# 2022.net
KiCad netlist of a schematic drawn in EAGLE
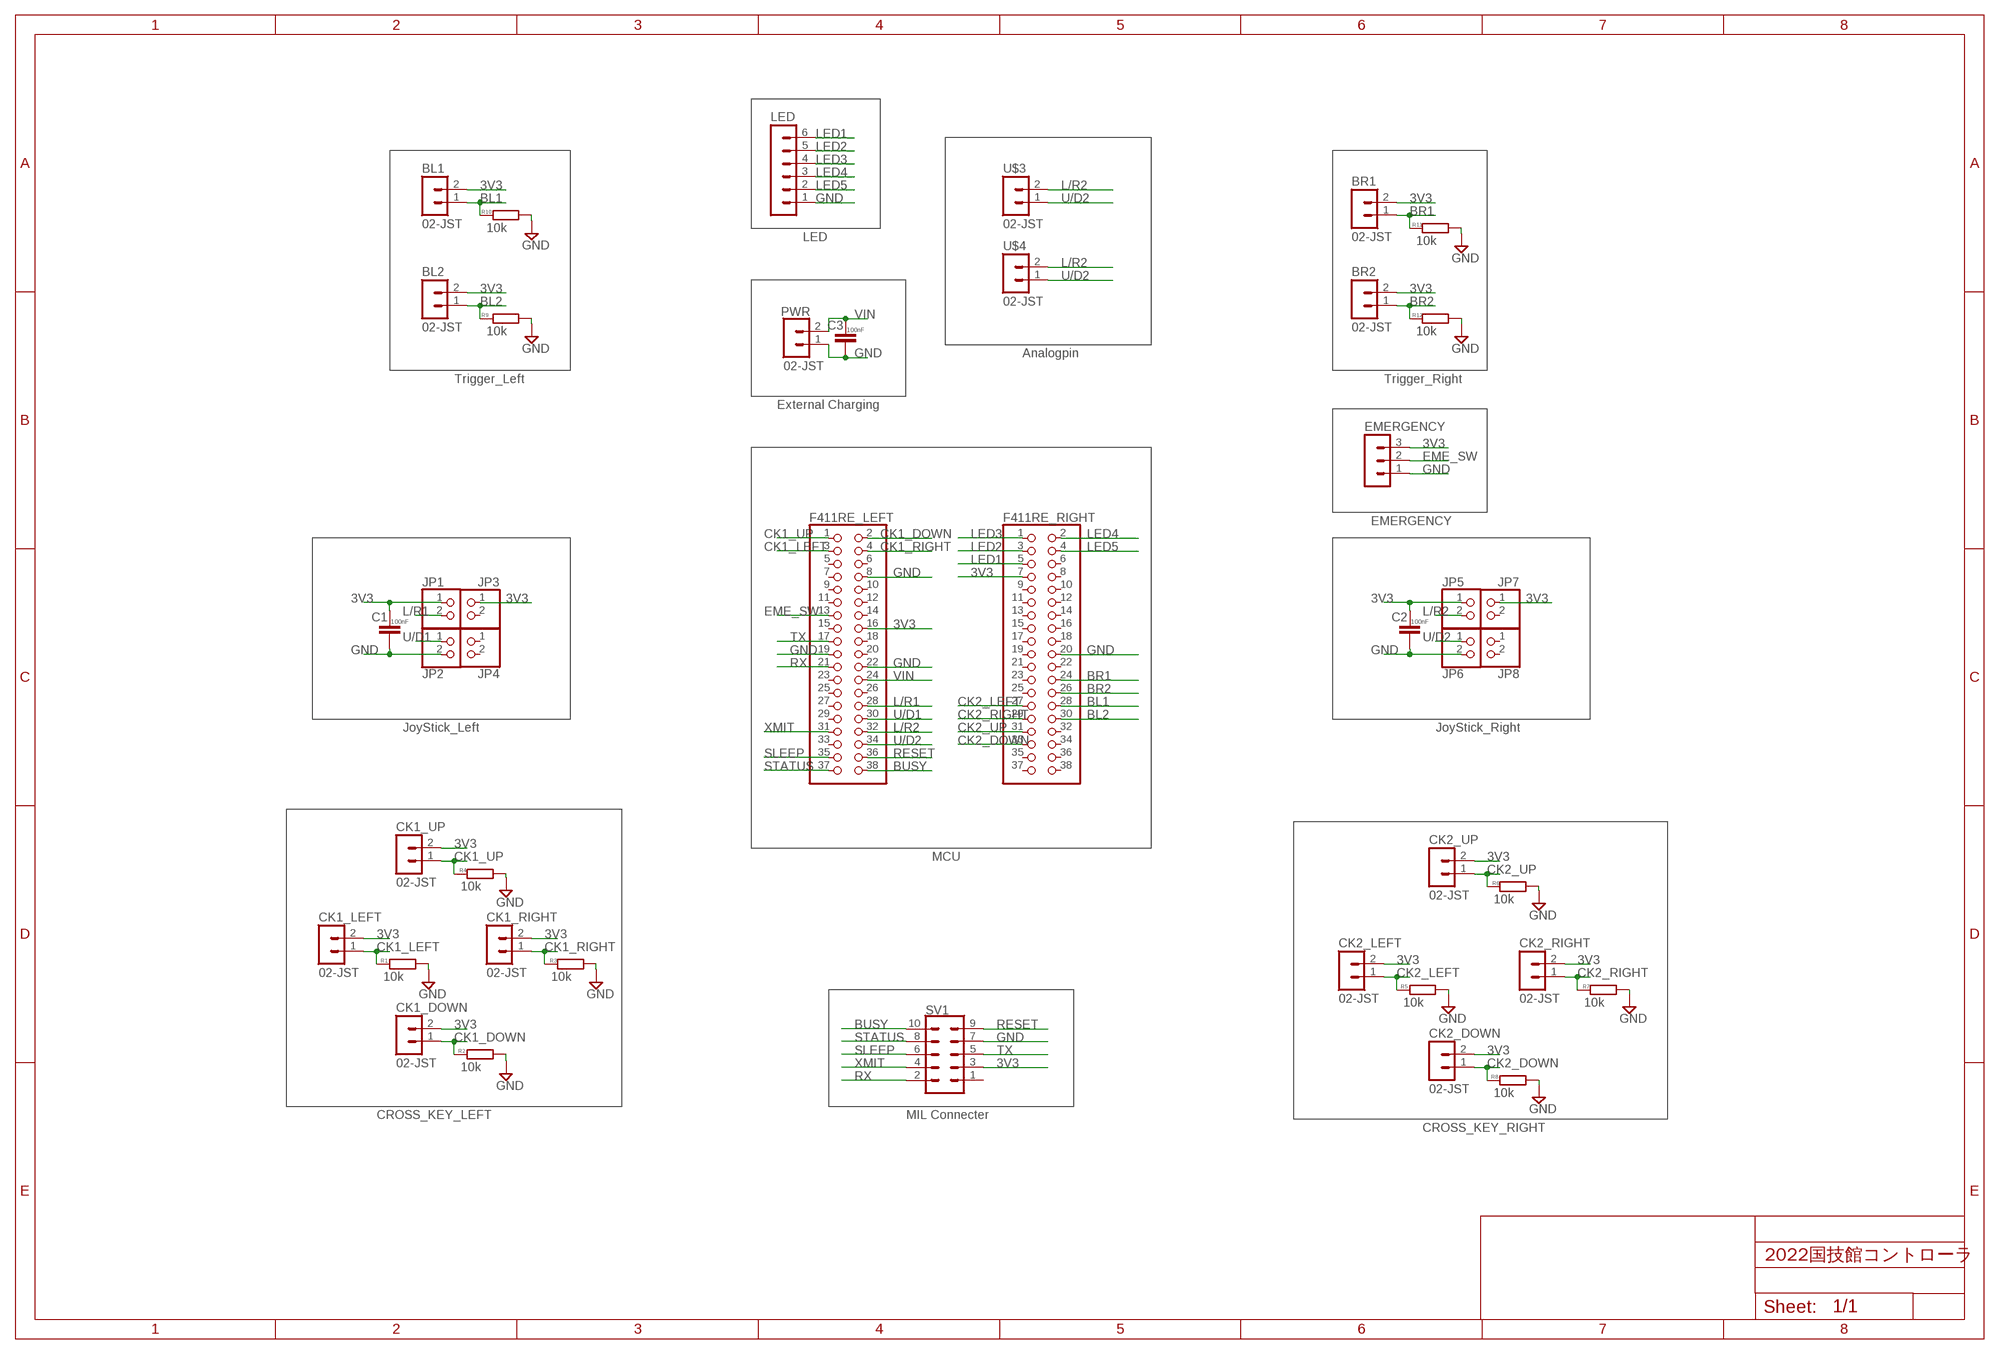
[diagram p0: schematic, sheet 1]

(export (version "E")
  (design (tool "Eeschema 10.0.6"))
  (components
    (comp (ref "BL1")
      (value "02-JST")
      (footprint "eagle-import:B2B-XH")
      (libsource (lib "eagle-import") (part "02-JST"))
    )
    (comp (ref "BL2")
      (value "02-JST")
      (footprint "eagle-import:B2B-XH")
      (libsource (lib "eagle-import") (part "02-JST"))
    )
    (comp (ref "BR1")
      (value "02-JST")
      (footprint "eagle-import:B2B-XH")
      (libsource (lib "eagle-import") (part "02-JST"))
    )
    (comp (ref "BR2")
      (value "02-JST")
      (footprint "eagle-import:B2B-XH")
      (libsource (lib "eagle-import") (part "02-JST"))
    )
    (comp (ref "C1")
      (value "100nF")
      (footprint "eagle-import:C025-024X044")
      (libsource (lib "eagle-import") (part "C-EU025-024X044"))
    )
    (comp (ref "C2")
      (value "100nF")
      (footprint "eagle-import:C025-024X044")
      (libsource (lib "eagle-import") (part "C-EU025-024X044"))
    )
    (comp (ref "C3")
      (value "100nF")
      (footprint "eagle-import:C025-024X044")
      (libsource (lib "eagle-import") (part "C-EU025-024X044"))
    )
    (comp (ref "CK1_DOWN")
      (value "02-JST")
      (footprint "eagle-import:B2B-XH")
      (libsource (lib "eagle-import") (part "02-JST"))
    )
    (comp (ref "CK1_LEFT")
      (value "02-JST")
      (footprint "eagle-import:B2B-XH")
      (libsource (lib "eagle-import") (part "02-JST"))
    )
    (comp (ref "CK1_RIGHT")
      (value "02-JST")
      (footprint "eagle-import:B2B-XH")
      (libsource (lib "eagle-import") (part "02-JST"))
    )
    (comp (ref "CK1_UP")
      (value "02-JST")
      (footprint "eagle-import:B2B-XH")
      (libsource (lib "eagle-import") (part "02-JST"))
    )
    (comp (ref "CK2_DOWN")
      (value "02-JST")
      (footprint "eagle-import:B2B-XH")
      (libsource (lib "eagle-import") (part "02-JST"))
    )
    (comp (ref "CK2_LEFT")
      (value "02-JST")
      (footprint "eagle-import:B2B-XH")
      (libsource (lib "eagle-import") (part "02-JST"))
    )
    (comp (ref "CK2_RIGHT")
      (value "02-JST")
      (footprint "eagle-import:B2B-XH")
      (libsource (lib "eagle-import") (part "02-JST"))
    )
    (comp (ref "CK2_UP")
      (value "02-JST")
      (footprint "eagle-import:B2B-XH")
      (libsource (lib "eagle-import") (part "02-JST"))
    )
    (comp (ref "EMERGENCY")
      (value "03-JST")
      (footprint "eagle-import:B3B-XH")
      (libsource (lib "eagle-import") (part "03-JST"))
    )
    (comp (ref "F411RE_LEFT")
      (value "PINHD-2X19")
      (footprint "eagle-import:2X19")
      (libsource (lib "eagle-import") (part "PINHD-2X19"))
    )
    (comp (ref "F411RE_RIGHT")
      (value "PINHD-2X19")
      (footprint "eagle-import:2X19")
      (libsource (lib "eagle-import") (part "PINHD-2X19"))
    )
    (comp (ref "JP1")
      (value "PINHD-1X2")
      (footprint "eagle-import:1X02")
      (libsource (lib "eagle-import") (part "PINHD-1X2"))
    )
    (comp (ref "JP2")
      (value "PINHD-1X2")
      (footprint "eagle-import:1X02")
      (libsource (lib "eagle-import") (part "PINHD-1X2"))
    )
    (comp (ref "JP3")
      (value "PINHD-1X2")
      (footprint "eagle-import:1X02")
      (libsource (lib "eagle-import") (part "PINHD-1X2"))
    )
    (comp (ref "JP4")
      (value "PINHD-1X2")
      (footprint "eagle-import:1X02")
      (libsource (lib "eagle-import") (part "PINHD-1X2"))
    )
    (comp (ref "JP5")
      (value "PINHD-1X2")
      (footprint "eagle-import:1X02")
      (libsource (lib "eagle-import") (part "PINHD-1X2"))
    )
    (comp (ref "JP6")
      (value "PINHD-1X2")
      (footprint "eagle-import:1X02")
      (libsource (lib "eagle-import") (part "PINHD-1X2"))
    )
    (comp (ref "JP7")
      (value "PINHD-1X2")
      (footprint "eagle-import:1X02")
      (libsource (lib "eagle-import") (part "PINHD-1X2"))
    )
    (comp (ref "JP8")
      (value "PINHD-1X2")
      (footprint "eagle-import:1X02")
      (libsource (lib "eagle-import") (part "PINHD-1X2"))
    )
    (comp (ref "LED")
      (value "06-JST")
      (footprint "eagle-import:B6B-XH")
      (libsource (lib "eagle-import") (part "06-JST"))
    )
    (comp (ref "PWR")
      (value "02-JST")
      (footprint "eagle-import:B2B-XH")
      (libsource (lib "eagle-import") (part "con-jst-xh (1)_02-JST"))
    )
    (comp (ref "R1")
      (value "10k")
      (footprint "eagle-import:0204_7")
      (libsource (lib "eagle-import") (part "R-EU_0204/7"))
    )
    (comp (ref "R2")
      (value "10k")
      (footprint "eagle-import:0204_7")
      (libsource (lib "eagle-import") (part "R-EU_0204/7"))
    )
    (comp (ref "R3")
      (value "10k")
      (footprint "eagle-import:0204_7")
      (libsource (lib "eagle-import") (part "R-EU_0204/7"))
    )
    (comp (ref "R4")
      (value "10k")
      (footprint "eagle-import:0204_7")
      (libsource (lib "eagle-import") (part "R-EU_0204/7"))
    )
    (comp (ref "R5")
      (value "10k")
      (footprint "eagle-import:0204_7")
      (libsource (lib "eagle-import") (part "R-EU_0204/7"))
    )
    (comp (ref "R6")
      (value "10k")
      (footprint "eagle-import:0204_7")
      (libsource (lib "eagle-import") (part "R-EU_0204/7"))
    )
    (comp (ref "R7")
      (value "10k")
      (footprint "eagle-import:0204_7")
      (libsource (lib "eagle-import") (part "R-EU_0204/7"))
    )
    (comp (ref "R8")
      (value "10k")
      (footprint "eagle-import:0204_7")
      (libsource (lib "eagle-import") (part "R-EU_0204/7"))
    )
    (comp (ref "R9")
      (value "10k")
      (footprint "eagle-import:0204_7")
      (libsource (lib "eagle-import") (part "R-EU_0204/7"))
    )
    (comp (ref "R10")
      (value "10k")
      (footprint "eagle-import:0204_7")
      (libsource (lib "eagle-import") (part "R-EU_0204/7"))
    )
    (comp (ref "R11")
      (value "10k")
      (footprint "eagle-import:0204_7")
      (libsource (lib "eagle-import") (part "R-EU_0204/7"))
    )
    (comp (ref "R12")
      (value "10k")
      (footprint "eagle-import:0204_7")
      (libsource (lib "eagle-import") (part "R-EU_0204/7"))
    )
    (comp (ref "SV1")
      (value "ML10")
      (footprint "eagle-import:ML10")
      (libsource (lib "eagle-import") (part "ML10"))
    )
    (comp (ref "U$3")
      (value "02-JST")
      (footprint "eagle-import:B2B-XH")
      (libsource (lib "eagle-import") (part "con-jst-xh (1)_02-JST"))
    )
    (comp (ref "U$4")
      (value "02-JST")
      (footprint "eagle-import:B2B-XH")
      (libsource (lib "eagle-import") (part "con-jst-xh (1)_02-JST"))
    )
  )
  (nets
    (net (code "1") (name "/3V3") (class "Default")
      (node (ref "BL1") (pin "2") (pinfunction "2_2") (pintype "passive"))
      (node (ref "BL2") (pin "2") (pinfunction "2_2") (pintype "passive"))
      (node (ref "BR1") (pin "2") (pinfunction "2_2") (pintype "passive"))
      (node (ref "BR2") (pin "2") (pinfunction "2_2") (pintype "passive"))
      (node (ref "C1") (pin "1") (pinfunction "1_1") (pintype "passive"))
      (node (ref "C2") (pin "1") (pinfunction "1_1") (pintype "passive"))
      (node (ref "CK1_DOWN") (pin "2") (pinfunction "2_2") (pintype "passive"))
      (node (ref "CK1_LEFT") (pin "2") (pinfunction "2_2") (pintype "passive"))
      (node (ref "CK1_RIGHT") (pin "2") (pinfunction "2_2") (pintype "passive"))
      (node (ref "CK1_UP") (pin "2") (pinfunction "2_2") (pintype "passive"))
      (node (ref "CK2_DOWN") (pin "2") (pinfunction "2_2") (pintype "passive"))
      (node (ref "CK2_LEFT") (pin "2") (pinfunction "2_2") (pintype "passive"))
      (node (ref "CK2_RIGHT") (pin "2") (pinfunction "2_2") (pintype "passive"))
      (node (ref "CK2_UP") (pin "2") (pinfunction "2_2") (pintype "passive"))
      (node (ref "EMERGENCY") (pin "3") (pinfunction "3_3") (pintype "passive"))
      (node (ref "F411RE_LEFT") (pin "16") (pinfunction "16_16") (pintype "passive"))
      (node (ref "F411RE_RIGHT") (pin "7") (pinfunction "7_7") (pintype "passive"))
      (node (ref "JP1") (pin "1") (pinfunction "1_1") (pintype "passive"))
      (node (ref "JP3") (pin "1") (pinfunction "1_1") (pintype "passive"))
      (node (ref "JP5") (pin "1") (pinfunction "1_1") (pintype "passive"))
      (node (ref "JP7") (pin "1") (pinfunction "1_1") (pintype "passive"))
      (node (ref "SV1") (pin "3") (pinfunction "3_3") (pintype "passive"))
    )
    (net (code "2") (name "/BL1") (class "Default")
      (node (ref "BL1") (pin "1") (pinfunction "1_1") (pintype "passive"))
      (node (ref "F411RE_RIGHT") (pin "28") (pinfunction "28_28") (pintype "passive"))
      (node (ref "R10") (pin "1") (pinfunction "1_1") (pintype "passive"))
    )
    (net (code "3") (name "/BL2") (class "Default")
      (node (ref "BL2") (pin "1") (pinfunction "1_1") (pintype "passive"))
      (node (ref "F411RE_RIGHT") (pin "30") (pinfunction "30_30") (pintype "passive"))
      (node (ref "R9") (pin "1") (pinfunction "1_1") (pintype "passive"))
    )
    (net (code "4") (name "/BR1") (class "Default")
      (node (ref "BR1") (pin "1") (pinfunction "1_1") (pintype "passive"))
      (node (ref "F411RE_RIGHT") (pin "24") (pinfunction "24_24") (pintype "passive"))
      (node (ref "R11") (pin "1") (pinfunction "1_1") (pintype "passive"))
    )
    (net (code "5") (name "/BR2") (class "Default")
      (node (ref "BR2") (pin "1") (pinfunction "1_1") (pintype "passive"))
      (node (ref "F411RE_RIGHT") (pin "26") (pinfunction "26_26") (pintype "passive"))
      (node (ref "R12") (pin "1") (pinfunction "1_1") (pintype "passive"))
    )
    (net (code "6") (name "/BUSY") (class "Default")
      (node (ref "F411RE_LEFT") (pin "38") (pinfunction "38_38") (pintype "passive"))
      (node (ref "SV1") (pin "10") (pinfunction "10_10") (pintype "passive"))
    )
    (net (code "7") (name "/CK1_DOWN") (class "Default")
      (node (ref "CK1_DOWN") (pin "1") (pinfunction "1_1") (pintype "passive"))
      (node (ref "F411RE_LEFT") (pin "2") (pinfunction "2_2") (pintype "passive"))
      (node (ref "R2") (pin "1") (pinfunction "1_1") (pintype "passive"))
    )
    (net (code "8") (name "/CK1_LEFT") (class "Default")
      (node (ref "CK1_LEFT") (pin "1") (pinfunction "1_1") (pintype "passive"))
      (node (ref "F411RE_LEFT") (pin "3") (pinfunction "3_3") (pintype "passive"))
      (node (ref "R1") (pin "1") (pinfunction "1_1") (pintype "passive"))
    )
    (net (code "9") (name "/CK1_RIGHT") (class "Default")
      (node (ref "CK1_RIGHT") (pin "1") (pinfunction "1_1") (pintype "passive"))
      (node (ref "F411RE_LEFT") (pin "4") (pinfunction "4_4") (pintype "passive"))
      (node (ref "R3") (pin "1") (pinfunction "1_1") (pintype "passive"))
    )
    (net (code "10") (name "/CK1_UP") (class "Default")
      (node (ref "CK1_UP") (pin "1") (pinfunction "1_1") (pintype "passive"))
      (node (ref "F411RE_LEFT") (pin "1") (pinfunction "1_1") (pintype "passive"))
      (node (ref "R4") (pin "1") (pinfunction "1_1") (pintype "passive"))
    )
    (net (code "11") (name "/CK2_DOWN") (class "Default")
      (node (ref "CK2_DOWN") (pin "1") (pinfunction "1_1") (pintype "passive"))
      (node (ref "F411RE_RIGHT") (pin "33") (pinfunction "33_33") (pintype "passive"))
      (node (ref "R8") (pin "1") (pinfunction "1_1") (pintype "passive"))
    )
    (net (code "12") (name "/CK2_LEFT") (class "Default")
      (node (ref "CK2_LEFT") (pin "1") (pinfunction "1_1") (pintype "passive"))
      (node (ref "F411RE_RIGHT") (pin "27") (pinfunction "27_27") (pintype "passive"))
      (node (ref "R5") (pin "1") (pinfunction "1_1") (pintype "passive"))
    )
    (net (code "13") (name "/CK2_RIGHT") (class "Default")
      (node (ref "CK2_RIGHT") (pin "1") (pinfunction "1_1") (pintype "passive"))
      (node (ref "F411RE_RIGHT") (pin "29") (pinfunction "29_29") (pintype "passive"))
      (node (ref "R7") (pin "1") (pinfunction "1_1") (pintype "passive"))
    )
    (net (code "14") (name "/CK2_UP") (class "Default")
      (node (ref "CK2_UP") (pin "1") (pinfunction "1_1") (pintype "passive"))
      (node (ref "F411RE_RIGHT") (pin "31") (pinfunction "31_31") (pintype "passive"))
      (node (ref "R6") (pin "1") (pinfunction "1_1") (pintype "passive"))
    )
    (net (code "15") (name "/EME_SW") (class "Default")
      (node (ref "EMERGENCY") (pin "2") (pinfunction "2_2") (pintype "passive"))
      (node (ref "F411RE_LEFT") (pin "13") (pinfunction "13_13") (pintype "passive"))
    )
    (net (code "16") (name "/LED1") (class "Default")
      (node (ref "F411RE_RIGHT") (pin "5") (pinfunction "5_5") (pintype "passive"))
      (node (ref "LED") (pin "6") (pinfunction "6_6") (pintype "passive"))
    )
    (net (code "17") (name "/LED2") (class "Default")
      (node (ref "F411RE_RIGHT") (pin "3") (pinfunction "3_3") (pintype "passive"))
      (node (ref "LED") (pin "5") (pinfunction "5_5") (pintype "passive"))
    )
    (net (code "18") (name "/LED3") (class "Default")
      (node (ref "F411RE_RIGHT") (pin "1") (pinfunction "1_1") (pintype "passive"))
      (node (ref "LED") (pin "4") (pinfunction "4_4") (pintype "passive"))
    )
    (net (code "19") (name "/LED4") (class "Default")
      (node (ref "F411RE_RIGHT") (pin "2") (pinfunction "2_2") (pintype "passive"))
      (node (ref "LED") (pin "3") (pinfunction "3_3") (pintype "passive"))
    )
    (net (code "20") (name "/LED5") (class "Default")
      (node (ref "F411RE_RIGHT") (pin "4") (pinfunction "4_4") (pintype "passive"))
      (node (ref "LED") (pin "2") (pinfunction "2_2") (pintype "passive"))
    )
    (net (code "21") (name "/L{slash}R1") (class "Default")
      (node (ref "F411RE_LEFT") (pin "28") (pinfunction "28_28") (pintype "passive"))
      (node (ref "JP1") (pin "2") (pinfunction "2_2") (pintype "passive"))
    )
    (net (code "22") (name "/L{slash}R2") (class "Default")
      (node (ref "F411RE_LEFT") (pin "32") (pinfunction "32_32") (pintype "passive"))
      (node (ref "JP5") (pin "2") (pinfunction "2_2") (pintype "passive"))
      (node (ref "U$3") (pin "2") (pinfunction "2_2") (pintype "passive"))
      (node (ref "U$4") (pin "2") (pinfunction "2_2") (pintype "passive"))
    )
    (net (code "23") (name "/RESET") (class "Default")
      (node (ref "F411RE_LEFT") (pin "36") (pinfunction "36_36") (pintype "passive"))
      (node (ref "SV1") (pin "9") (pinfunction "9_9") (pintype "passive"))
    )
    (net (code "24") (name "/RX") (class "Default")
      (node (ref "F411RE_LEFT") (pin "21") (pinfunction "21_21") (pintype "passive"))
      (node (ref "SV1") (pin "2") (pinfunction "2_2") (pintype "passive"))
    )
    (net (code "25") (name "/SLEEP") (class "Default")
      (node (ref "F411RE_LEFT") (pin "35") (pinfunction "35_35") (pintype "passive"))
      (node (ref "SV1") (pin "6") (pinfunction "6_6") (pintype "passive"))
    )
    (net (code "26") (name "/STATUS") (class "Default")
      (node (ref "F411RE_LEFT") (pin "37") (pinfunction "37_37") (pintype "passive"))
      (node (ref "SV1") (pin "8") (pinfunction "8_8") (pintype "passive"))
    )
    (net (code "27") (name "/TX") (class "Default")
      (node (ref "F411RE_LEFT") (pin "17") (pinfunction "17_17") (pintype "passive"))
      (node (ref "SV1") (pin "5") (pinfunction "5_5") (pintype "passive"))
    )
    (net (code "28") (name "/U{slash}D1") (class "Default")
      (node (ref "F411RE_LEFT") (pin "30") (pinfunction "30_30") (pintype "passive"))
      (node (ref "JP2") (pin "1") (pinfunction "1_1") (pintype "passive"))
    )
    (net (code "29") (name "/U{slash}D2") (class "Default")
      (node (ref "F411RE_LEFT") (pin "34") (pinfunction "34_34") (pintype "passive"))
      (node (ref "JP6") (pin "1") (pinfunction "1_1") (pintype "passive"))
      (node (ref "U$3") (pin "1") (pinfunction "1_1") (pintype "passive"))
      (node (ref "U$4") (pin "1") (pinfunction "1_1") (pintype "passive"))
    )
    (net (code "30") (name "/VIN") (class "Default")
      (node (ref "C3") (pin "1") (pinfunction "1_1") (pintype "passive"))
      (node (ref "F411RE_LEFT") (pin "24") (pinfunction "24_24") (pintype "passive"))
      (node (ref "PWR") (pin "2") (pinfunction "2_2") (pintype "passive"))
    )
    (net (code "31") (name "/XMIT") (class "Default")
      (node (ref "F411RE_LEFT") (pin "31") (pinfunction "31_31") (pintype "passive"))
      (node (ref "SV1") (pin "4") (pinfunction "4_4") (pintype "passive"))
    )
    (net (code "32") (name "GND") (class "Default")
      (node (ref "C1") (pin "2") (pinfunction "2_2") (pintype "passive"))
      (node (ref "C2") (pin "2") (pinfunction "2_2") (pintype "passive"))
      (node (ref "C3") (pin "2") (pinfunction "2_2") (pintype "passive"))
      (node (ref "EMERGENCY") (pin "1") (pinfunction "1_1") (pintype "passive"))
      (node (ref "F411RE_LEFT") (pin "19") (pinfunction "19_19") (pintype "passive"))
      (node (ref "F411RE_LEFT") (pin "22") (pinfunction "22_22") (pintype "passive"))
      (node (ref "F411RE_LEFT") (pin "8") (pinfunction "8_8") (pintype "passive"))
      (node (ref "F411RE_RIGHT") (pin "20") (pinfunction "20_20") (pintype "passive"))
      (node (ref "JP2") (pin "2") (pinfunction "2_2") (pintype "passive"))
      (node (ref "JP6") (pin "2") (pinfunction "2_2") (pintype "passive"))
      (node (ref "LED") (pin "1") (pinfunction "1_1") (pintype "passive"))
      (node (ref "PWR") (pin "1") (pinfunction "1_1") (pintype "passive"))
      (node (ref "R1") (pin "2") (pinfunction "2_2") (pintype "passive"))
      (node (ref "R10") (pin "2") (pinfunction "2_2") (pintype "passive"))
      (node (ref "R11") (pin "2") (pinfunction "2_2") (pintype "passive"))
      (node (ref "R12") (pin "2") (pinfunction "2_2") (pintype "passive"))
      (node (ref "R2") (pin "2") (pinfunction "2_2") (pintype "passive"))
      (node (ref "R3") (pin "2") (pinfunction "2_2") (pintype "passive"))
      (node (ref "R4") (pin "2") (pinfunction "2_2") (pintype "passive"))
      (node (ref "R5") (pin "2") (pinfunction "2_2") (pintype "passive"))
      (node (ref "R6") (pin "2") (pinfunction "2_2") (pintype "passive"))
      (node (ref "R7") (pin "2") (pinfunction "2_2") (pintype "passive"))
      (node (ref "R8") (pin "2") (pinfunction "2_2") (pintype "passive"))
      (node (ref "R9") (pin "2") (pinfunction "2_2") (pintype "passive"))
      (node (ref "SV1") (pin "7") (pinfunction "7_7") (pintype "passive"))
    )
    (net (code "33") (name "unconnected-(F411RE_LEFT-Pad5)") (class "Default")
      (node (ref "F411RE_LEFT") (pin "5") (pinfunction "5_5") (pintype "passive"))
    )
    (net (code "34") (name "unconnected-(F411RE_LEFT-Pad6)") (class "Default")
      (node (ref "F411RE_LEFT") (pin "6") (pinfunction "6_6") (pintype "passive"))
    )
    (net (code "35") (name "unconnected-(F411RE_LEFT-Pad7)") (class "Default")
      (node (ref "F411RE_LEFT") (pin "7") (pinfunction "7_7") (pintype "passive"))
    )
    (net (code "36") (name "unconnected-(F411RE_LEFT-Pad9)") (class "Default")
      (node (ref "F411RE_LEFT") (pin "9") (pinfunction "9_9") (pintype "passive"))
    )
    (net (code "37") (name "unconnected-(F411RE_LEFT-Pad10)") (class "Default")
      (node (ref "F411RE_LEFT") (pin "10") (pinfunction "10_10") (pintype "passive"))
    )
    (net (code "38") (name "unconnected-(F411RE_LEFT-Pad11)") (class "Default")
      (node (ref "F411RE_LEFT") (pin "11") (pinfunction "11_11") (pintype "passive"))
    )
    (net (code "39") (name "unconnected-(F411RE_LEFT-Pad12)") (class "Default")
      (node (ref "F411RE_LEFT") (pin "12") (pinfunction "12_12") (pintype "passive"))
    )
    (net (code "40") (name "unconnected-(F411RE_LEFT-Pad14)") (class "Default")
      (node (ref "F411RE_LEFT") (pin "14") (pinfunction "14_14") (pintype "passive"))
    )
    (net (code "41") (name "unconnected-(F411RE_LEFT-Pad15)") (class "Default")
      (node (ref "F411RE_LEFT") (pin "15") (pinfunction "15_15") (pintype "passive"))
    )
    (net (code "42") (name "unconnected-(F411RE_LEFT-Pad18)") (class "Default")
      (node (ref "F411RE_LEFT") (pin "18") (pinfunction "18_18") (pintype "passive"))
    )
    (net (code "43") (name "unconnected-(F411RE_LEFT-Pad20)") (class "Default")
      (node (ref "F411RE_LEFT") (pin "20") (pinfunction "20_20") (pintype "passive"))
    )
    (net (code "44") (name "unconnected-(F411RE_LEFT-Pad23)") (class "Default")
      (node (ref "F411RE_LEFT") (pin "23") (pinfunction "23_23") (pintype "passive"))
    )
    (net (code "45") (name "unconnected-(F411RE_LEFT-Pad25)") (class "Default")
      (node (ref "F411RE_LEFT") (pin "25") (pinfunction "25_25") (pintype "passive"))
    )
    (net (code "46") (name "unconnected-(F411RE_LEFT-Pad26)") (class "Default")
      (node (ref "F411RE_LEFT") (pin "26") (pinfunction "26_26") (pintype "passive"))
    )
    (net (code "47") (name "unconnected-(F411RE_LEFT-Pad27)") (class "Default")
      (node (ref "F411RE_LEFT") (pin "27") (pinfunction "27_27") (pintype "passive"))
    )
    (net (code "48") (name "unconnected-(F411RE_LEFT-Pad29)") (class "Default")
      (node (ref "F411RE_LEFT") (pin "29") (pinfunction "29_29") (pintype "passive"))
    )
    (net (code "49") (name "unconnected-(F411RE_LEFT-Pad33)") (class "Default")
      (node (ref "F411RE_LEFT") (pin "33") (pinfunction "33_33") (pintype "passive"))
    )
    (net (code "50") (name "unconnected-(F411RE_RIGHT-Pad6)") (class "Default")
      (node (ref "F411RE_RIGHT") (pin "6") (pinfunction "6_6") (pintype "passive"))
    )
    (net (code "51") (name "unconnected-(F411RE_RIGHT-Pad8)") (class "Default")
      (node (ref "F411RE_RIGHT") (pin "8") (pinfunction "8_8") (pintype "passive"))
    )
    (net (code "52") (name "unconnected-(F411RE_RIGHT-Pad9)") (class "Default")
      (node (ref "F411RE_RIGHT") (pin "9") (pinfunction "9_9") (pintype "passive"))
    )
    (net (code "53") (name "unconnected-(F411RE_RIGHT-Pad10)") (class "Default")
      (node (ref "F411RE_RIGHT") (pin "10") (pinfunction "10_10") (pintype "passive"))
    )
    (net (code "54") (name "unconnected-(F411RE_RIGHT-Pad11)") (class "Default")
      (node (ref "F411RE_RIGHT") (pin "11") (pinfunction "11_11") (pintype "passive"))
    )
    (net (code "55") (name "unconnected-(F411RE_RIGHT-Pad12)") (class "Default")
      (node (ref "F411RE_RIGHT") (pin "12") (pinfunction "12_12") (pintype "passive"))
    )
    (net (code "56") (name "unconnected-(F411RE_RIGHT-Pad13)") (class "Default")
      (node (ref "F411RE_RIGHT") (pin "13") (pinfunction "13_13") (pintype "passive"))
    )
    (net (code "57") (name "unconnected-(F411RE_RIGHT-Pad14)") (class "Default")
      (node (ref "F411RE_RIGHT") (pin "14") (pinfunction "14_14") (pintype "passive"))
    )
    (net (code "58") (name "unconnected-(F411RE_RIGHT-Pad15)") (class "Default")
      (node (ref "F411RE_RIGHT") (pin "15") (pinfunction "15_15") (pintype "passive"))
    )
    (net (code "59") (name "unconnected-(F411RE_RIGHT-Pad16)") (class "Default")
      (node (ref "F411RE_RIGHT") (pin "16") (pinfunction "16_16") (pintype "passive"))
    )
    (net (code "60") (name "unconnected-(F411RE_RIGHT-Pad17)") (class "Default")
      (node (ref "F411RE_RIGHT") (pin "17") (pinfunction "17_17") (pintype "passive"))
    )
    (net (code "61") (name "unconnected-(F411RE_RIGHT-Pad18)") (class "Default")
      (node (ref "F411RE_RIGHT") (pin "18") (pinfunction "18_18") (pintype "passive"))
    )
    (net (code "62") (name "unconnected-(F411RE_RIGHT-Pad19)") (class "Default")
      (node (ref "F411RE_RIGHT") (pin "19") (pinfunction "19_19") (pintype "passive"))
    )
    (net (code "63") (name "unconnected-(F411RE_RIGHT-Pad21)") (class "Default")
      (node (ref "F411RE_RIGHT") (pin "21") (pinfunction "21_21") (pintype "passive"))
    )
    (net (code "64") (name "unconnected-(F411RE_RIGHT-Pad22)") (class "Default")
      (node (ref "F411RE_RIGHT") (pin "22") (pinfunction "22_22") (pintype "passive"))
    )
    (net (code "65") (name "unconnected-(F411RE_RIGHT-Pad23)") (class "Default")
      (node (ref "F411RE_RIGHT") (pin "23") (pinfunction "23_23") (pintype "passive"))
    )
    (net (code "66") (name "unconnected-(F411RE_RIGHT-Pad25)") (class "Default")
      (node (ref "F411RE_RIGHT") (pin "25") (pinfunction "25_25") (pintype "passive"))
    )
    (net (code "67") (name "unconnected-(F411RE_RIGHT-Pad32)") (class "Default")
      (node (ref "F411RE_RIGHT") (pin "32") (pinfunction "32_32") (pintype "passive"))
    )
    (net (code "68") (name "unconnected-(F411RE_RIGHT-Pad34)") (class "Default")
      (node (ref "F411RE_RIGHT") (pin "34") (pinfunction "34_34") (pintype "passive"))
    )
    (net (code "69") (name "unconnected-(F411RE_RIGHT-Pad35)") (class "Default")
      (node (ref "F411RE_RIGHT") (pin "35") (pinfunction "35_35") (pintype "passive"))
    )
    (net (code "70") (name "unconnected-(F411RE_RIGHT-Pad36)") (class "Default")
      (node (ref "F411RE_RIGHT") (pin "36") (pinfunction "36_36") (pintype "passive"))
    )
    (net (code "71") (name "unconnected-(F411RE_RIGHT-Pad37)") (class "Default")
      (node (ref "F411RE_RIGHT") (pin "37") (pinfunction "37_37") (pintype "passive"))
    )
    (net (code "72") (name "unconnected-(F411RE_RIGHT-Pad38)") (class "Default")
      (node (ref "F411RE_RIGHT") (pin "38") (pinfunction "38_38") (pintype "passive"))
    )
    (net (code "73") (name "unconnected-(JP3-Pad2)") (class "Default")
      (node (ref "JP3") (pin "2") (pinfunction "2_2") (pintype "passive"))
    )
    (net (code "74") (name "unconnected-(JP4-Pad1)") (class "Default")
      (node (ref "JP4") (pin "1") (pinfunction "1_1") (pintype "passive"))
    )
    (net (code "75") (name "unconnected-(JP4-Pad2)") (class "Default")
      (node (ref "JP4") (pin "2") (pinfunction "2_2") (pintype "passive"))
    )
    (net (code "76") (name "unconnected-(JP7-Pad2)") (class "Default")
      (node (ref "JP7") (pin "2") (pinfunction "2_2") (pintype "passive"))
    )
    (net (code "77") (name "unconnected-(JP8-Pad1)") (class "Default")
      (node (ref "JP8") (pin "1") (pinfunction "1_1") (pintype "passive"))
    )
    (net (code "78") (name "unconnected-(JP8-Pad2)") (class "Default")
      (node (ref "JP8") (pin "2") (pinfunction "2_2") (pintype "passive"))
    )
    (net (code "79") (name "unconnected-(SV1-Pad1)") (class "Default")
      (node (ref "SV1") (pin "1") (pinfunction "1_1") (pintype "passive"))
    )
  )
)
